# SCH_plytka01_2023-10-24.net
KiCad netlist of a schematic drawn in EasyEDA
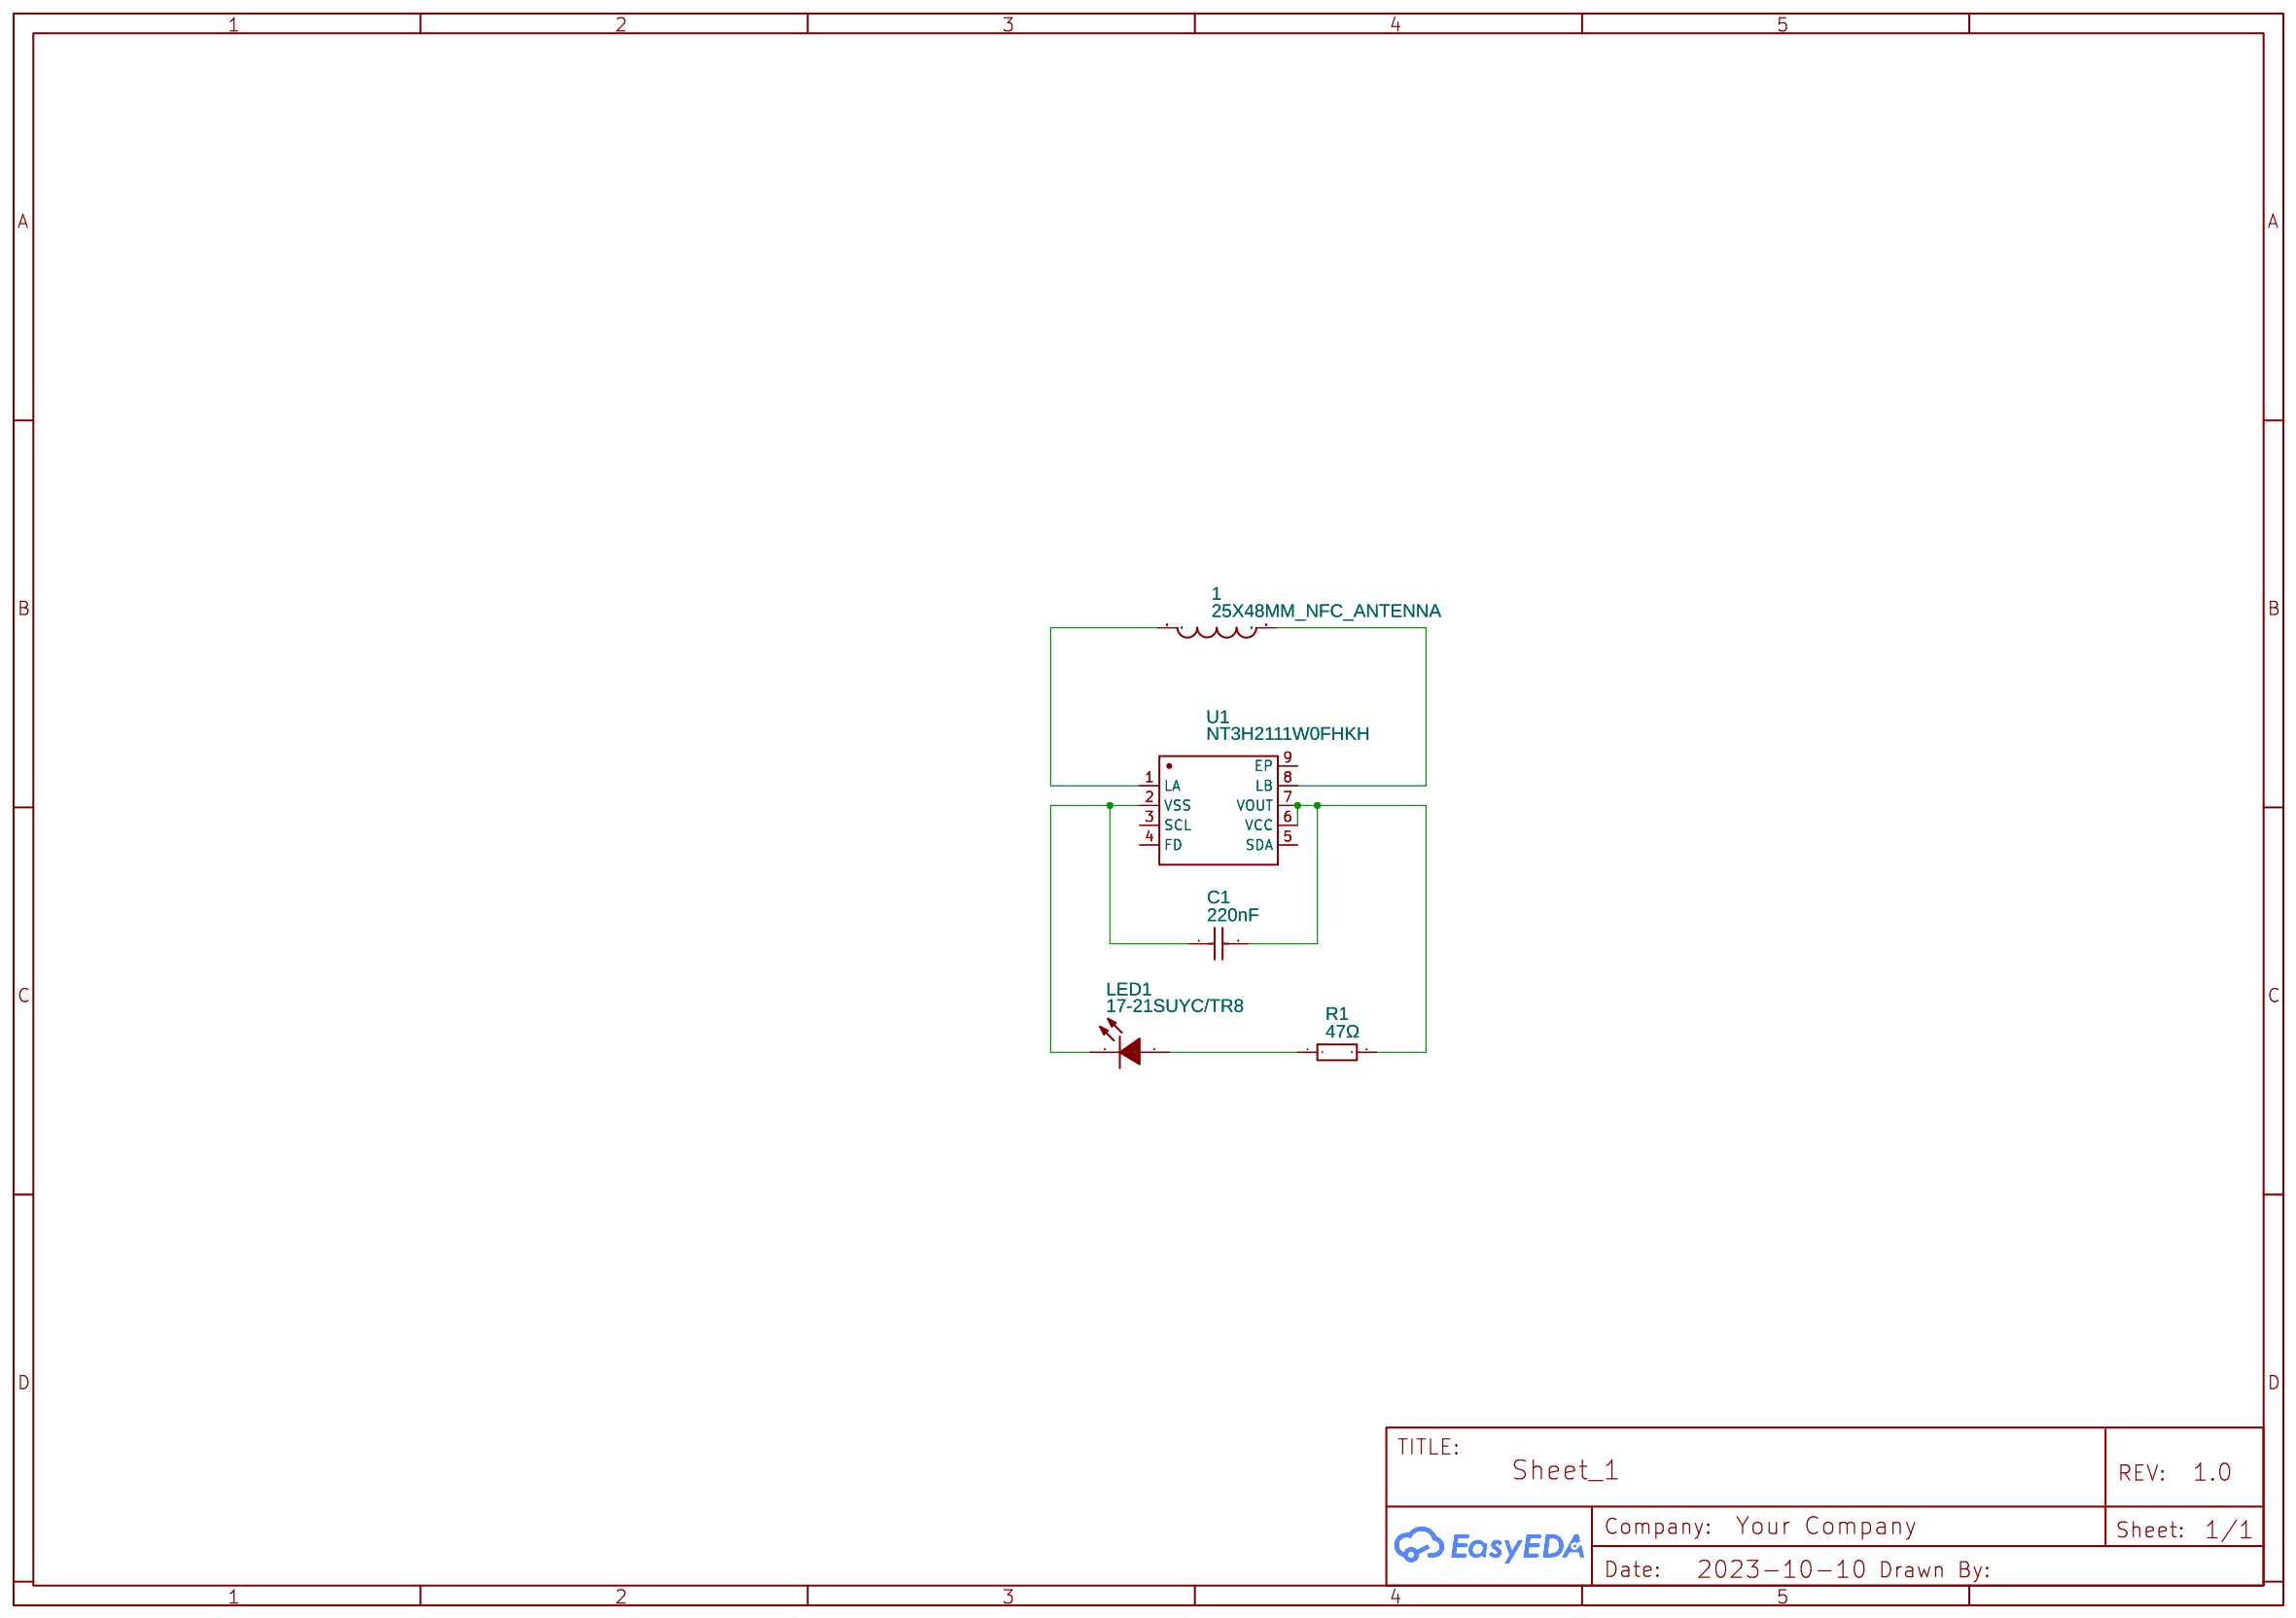
[diagram p0: schematic sheet]

(export (version "E")
  (design (tool "Eeschema 10.0.6"))
  (components
    (comp (ref "1") (value "25X48MM_NFC_ANTENNA") (libsource (lib "") (part "25X48MM_NFC_ANTENNA")))
    (comp (ref "C1")
      (value "220nF")
      (fields
        (field (name "Manufacturer Part") "CL10B224KA8NNNC")
        (field (name "Manufacturer") "SAMSUNG(三星)")
      )
      (libsource (lib "") (part "CL10B224KA8NNNC"))
    )
    (comp (ref "LED1")
      (value "17-21SUYC/TR8")
      (fields (field (name "Manufacturer Part") "KT-0805黄灯") (field (name "Manufacturer") "KENTO"))
      (libsource (lib "") (part "17-21SUYC/TR8"))
    )
    (comp (ref "R1")
      (value "47Ω")
      (fields
        (field (name "Manufacturer Part") "0603WAF470JT5E")
        (field (name "Manufacturer") "UNI-ROYAL(厚声)")
      )
      (libsource (lib "") (part "0603WAF470JT5E"))
    )
    (comp (ref "U1")
      (value "NT3H2111W0FHKH")
      (fields (field (name "Manufacturer") "NXP(恩智浦)"))
      (libsource (lib "") (part "NT3H2111W0FHKH"))
    )
  )
  (nets
    (net (code "1") (name "Net-(LED1-+)") (class "Default")
      (node (ref "LED1") (pin "1") (pinfunction "+_1") (pintype "unspecified"))
      (node (ref "R1") (pin "1") (pinfunction "1_1") (pintype "input"))
    )
    (net (code "2") (name "Net-(LED1--)") (class "Default")
      (node (ref "C1") (pin "1") (pinfunction "1_1") (pintype "input"))
      (node (ref "LED1") (pin "2") (pinfunction "-_2") (pintype "unspecified"))
      (node (ref "U1") (pin "2") (pinfunction "VSS_2") (pintype "unspecified"))
    )
    (net (code "3") (name "Net-(U1-LA)") (class "Default")
      (node (ref "1") (pin "P$2") (pinfunction "P$2_P$2") (pintype "bidirectional"))
      (node (ref "U1") (pin "1") (pinfunction "LA_1") (pintype "unspecified"))
    )
    (net (code "4") (name "Net-(U1-LB)") (class "Default")
      (node (ref "1") (pin "P$1") (pinfunction "P$1_P$1") (pintype "bidirectional"))
      (node (ref "U1") (pin "8") (pinfunction "LB_8") (pintype "unspecified"))
    )
    (net (code "5") (name "Net-(U1-VCC)") (class "Default")
      (node (ref "C1") (pin "2") (pinfunction "2_2") (pintype "input"))
      (node (ref "R1") (pin "2") (pinfunction "2_2") (pintype "input"))
      (node (ref "U1") (pin "6") (pinfunction "VCC_6") (pintype "unspecified"))
      (node (ref "U1") (pin "7") (pinfunction "VOUT_7") (pintype "unspecified"))
    )
    (net (code "6") (name "unconnected-(U1-EP-Pad9)") (class "Default")
      (node (ref "U1") (pin "9") (pinfunction "EP_9") (pintype "unspecified"))
    )
    (net (code "7") (name "unconnected-(U1-FD-Pad4)") (class "Default")
      (node (ref "U1") (pin "4") (pinfunction "FD_4") (pintype "unspecified"))
    )
    (net (code "8") (name "unconnected-(U1-SCL-Pad3)") (class "Default")
      (node (ref "U1") (pin "3") (pinfunction "SCL_3") (pintype "unspecified"))
    )
    (net (code "9") (name "unconnected-(U1-SDA-Pad5)") (class "Default")
      (node (ref "U1") (pin "5") (pinfunction "SDA_5") (pintype "unspecified"))
    )
  )
)
